# Power.net
KiCad netlist of a schematic drawn in Altium Designer
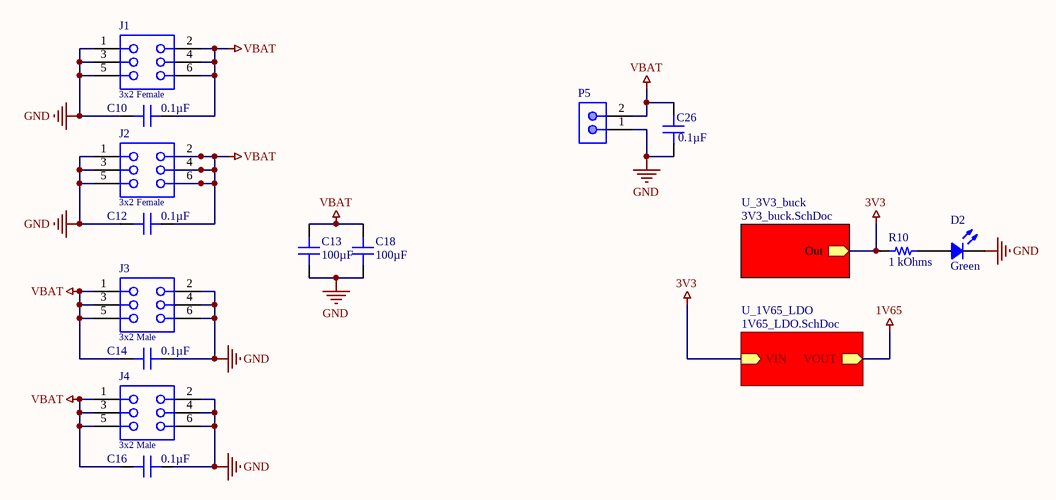
[diagram p0: Power.SchDoc]

(export (version "E")
  (design (tool "Eeschema 10.0.6"))
  (components
    (comp (ref "C10")
      (value "0.1µF")
      (footprint "CAP 0603_1608")
      (description "CAP CER 0.1UF 100V 0603 EPOXY")
      (fields
        (field (name "PART NUMBER") "GCG188R92A104KA03D")
        (field (name "MANUFACTURER") "Murata Electronics")
      )
      (libsource (lib "Celestial Altium Library - altium_library") (part "Capacitor"))
    )
    (comp (ref "C12")
      (value "0.1µF")
      (footprint "CAP 0603_1608")
      (description "CAP CER 0.1UF 100V 0603 EPOXY")
      (fields
        (field (name "PART NUMBER") "GCG188R92A104KA03D")
        (field (name "MANUFACTURER") "Murata Electronics")
      )
      (libsource (lib "Celestial Altium Library - altium_library") (part "Capacitor"))
    )
    (comp (ref "C13")
      (value "100µF")
      (footprint "CAP 1210_3225 - 2.8MM")
      (description "CAP CER 100UF 16V X5R 1210")
      (fields (field (name "PART NUMBER") "EMK325ABJ107MM-P") (field (name "MANUFACTURER") "Taiyo Yuden"))
      (libsource (lib "Celestial Altium Library - altium_library") (part "Capacitor"))
    )
    (comp (ref "C14")
      (value "0.1µF")
      (footprint "CAP 0603_1608")
      (description "CAP CER 0.1UF 100V 0603 EPOXY")
      (fields
        (field (name "PART NUMBER") "GCG188R92A104KA03D")
        (field (name "MANUFACTURER") "Murata Electronics")
      )
      (libsource (lib "Celestial Altium Library - altium_library") (part "Capacitor"))
    )
    (comp (ref "C16")
      (value "0.1µF")
      (footprint "CAP 0603_1608")
      (description "CAP CER 0.1UF 100V 0603 EPOXY")
      (fields
        (field (name "PART NUMBER") "GCG188R92A104KA03D")
        (field (name "MANUFACTURER") "Murata Electronics")
      )
      (libsource (lib "Celestial Altium Library - altium_library") (part "Capacitor"))
    )
    (comp (ref "C18")
      (value "100µF")
      (footprint "CAP 1210_3225 - 2.8MM")
      (description "CAP CER 100UF 16V X5R 1210")
      (fields (field (name "PART NUMBER") "EMK325ABJ107MM-P") (field (name "MANUFACTURER") "Taiyo Yuden"))
      (libsource (lib "Celestial Altium Library - altium_library") (part "Capacitor"))
    )
    (comp (ref "C26")
      (value "0.1µF")
      (footprint "CAP 0603_1608")
      (description "CAP CER 0.1UF 100V 0603 EPOXY")
      (fields
        (field (name "PART NUMBER") "GCG188R92A104KA03D")
        (field (name "MANUFACTURER") "Murata Electronics")
      )
      (libsource (lib "Celestial Altium Library - altium_library") (part "Capacitor"))
    )
    (comp (ref "D2")
      (value "Green")
      (footprint "LED 0603_1608 GREEN")
      (description "1.6X0.8MM LC GREEN PIXSOLED DOME")
      (fields (field (name "PART NUMBER") "XZCDGK53W-8VF") (field (name "MANUFACTURER") "SunLED"))
      (libsource (lib "Celestial Altium Library - altium_library") (part "LED"))
    )
    (comp (ref "J1")
      (value "3x2 Female")
      (footprint "62000621821")
      (description "WR-PHD Socket Header, THT, pitch 2mm, Dual Row, Vertical, 6p")
      (fields
        (field (name "MANUFACTURER PART NUMBER") "62000621821")
        (field (name "MANUFACTURER") "Wurth Elektronik")
      )
      (libsource (lib "Altium_WR-PHD") (part "62000621821"))
    )
    (comp (ref "J2")
      (value "3x2 Female")
      (footprint "62000621821")
      (description "WR-PHD Socket Header, THT, pitch 2mm, Dual Row, Vertical, 6p")
      (fields
        (field (name "MANUFACTURER PART NUMBER") "62000621821")
        (field (name "MANUFACTURER") "Wurth Elektronik")
      )
      (libsource (lib "Altium_WR-PHD") (part "62000621821"))
    )
    (comp (ref "J3")
      (value "3x2 Male")
      (footprint "2mm 3x2 Male Right - duplicate")
      (description "2mm Male 3x2 Right")
      (fields
        (field (name "MANUFACTURER PART NUMBER") "62000621821")
        (field (name "MANUFACTURER") "Wurth Elektronik")
      )
      (libsource (lib "IC") (part "2mm Male 3x2 Right"))
    )
    (comp (ref "J4")
      (value "3x2 Male")
      (footprint "2mm 3x2 Male Right - duplicate")
      (description "2mm Male 3x2 Right")
      (fields
        (field (name "MANUFACTURER PART NUMBER") "62000621821")
        (field (name "MANUFACTURER") "Wurth Elektronik")
      )
      (libsource (lib "IC") (part "2mm Male 3x2 Right"))
    )
    (comp (ref "P5")
      (value "2 pin 2mm JST Male")
      (footprint "2pin - 2mm JST male")
      (libsource (lib "IC") (part "2 pin 2mm JST Male"))
    )
    (comp (ref "R10")
      (value "1 kOhms")
      (footprint "RES 0603_1608")
      (description "RES 1K OHM 0.5% 1/10W 0603")
      (fields
        (field (name "PART NUMBER") "RNCF0603DTE1K00")
        (field (name "MANUFACTURER") "Stackpole Electronics Inc")
      )
      (libsource (lib "Celestial Altium Library - altium_library") (part "Resistor"))
    )
  )
  (nets
    (net (code "2") (name "3V3") (class "Default")
      (node (ref "R10") (pin "1") (pinfunction "1_1") (pintype "passive"))
    )
    (net (code "3") (name "GND") (class "Default")
      (node (ref "C10") (pin "1") (pinfunction "1_1") (pintype "passive"))
      (node (ref "C12") (pin "1") (pinfunction "1_1") (pintype "passive"))
      (node (ref "C13") (pin "1") (pinfunction "1_1") (pintype "passive"))
      (node (ref "C14") (pin "2") (pinfunction "2_2") (pintype "passive"))
      (node (ref "C16") (pin "2") (pinfunction "2_2") (pintype "passive"))
      (node (ref "C18") (pin "1") (pinfunction "1_1") (pintype "passive"))
      (node (ref "C26") (pin "2") (pinfunction "2_2") (pintype "passive"))
      (node (ref "D2") (pin "2") (pinfunction "2_2") (pintype "passive"))
      (node (ref "J1") (pin "1") (pinfunction "1_1") (pintype "passive"))
      (node (ref "J1") (pin "3") (pinfunction "3_3") (pintype "passive"))
      (node (ref "J1") (pin "5") (pinfunction "5_5") (pintype "passive"))
      (node (ref "J2") (pin "1") (pinfunction "1_1") (pintype "passive"))
      (node (ref "J2") (pin "3") (pinfunction "3_3") (pintype "passive"))
      (node (ref "J2") (pin "5") (pinfunction "5_5") (pintype "passive"))
      (node (ref "J3") (pin "2") (pinfunction "2_2") (pintype "passive"))
      (node (ref "J3") (pin "4") (pinfunction "4_4") (pintype "passive"))
      (node (ref "J3") (pin "6") (pinfunction "6_6") (pintype "passive"))
      (node (ref "J4") (pin "2") (pinfunction "2_2") (pintype "passive"))
      (node (ref "J4") (pin "4") (pinfunction "4_4") (pintype "passive"))
      (node (ref "J4") (pin "6") (pinfunction "6_6") (pintype "passive"))
      (node (ref "P5") (pin "1") (pinfunction "1_1") (pintype "passive"))
    )
    (net (code "4") (name "Net-(D2-Pad1)") (class "Default")
      (node (ref "D2") (pin "1") (pinfunction "1_1") (pintype "passive"))
      (node (ref "R10") (pin "2") (pinfunction "2_2") (pintype "passive"))
    )
    (net (code "5") (name "VBAT") (class "Default")
      (node (ref "C10") (pin "2") (pinfunction "2_2") (pintype "passive"))
      (node (ref "C12") (pin "2") (pinfunction "2_2") (pintype "passive"))
      (node (ref "C13") (pin "2") (pinfunction "2_2") (pintype "passive"))
      (node (ref "C14") (pin "1") (pinfunction "1_1") (pintype "passive"))
      (node (ref "C16") (pin "1") (pinfunction "1_1") (pintype "passive"))
      (node (ref "C18") (pin "2") (pinfunction "2_2") (pintype "passive"))
      (node (ref "C26") (pin "1") (pinfunction "1_1") (pintype "passive"))
      (node (ref "J1") (pin "2") (pinfunction "2_2") (pintype "passive"))
      (node (ref "J1") (pin "4") (pinfunction "4_4") (pintype "passive"))
      (node (ref "J1") (pin "6") (pinfunction "6_6") (pintype "passive"))
      (node (ref "J2") (pin "2") (pinfunction "2_2") (pintype "passive"))
      (node (ref "J2") (pin "4") (pinfunction "4_4") (pintype "passive"))
      (node (ref "J2") (pin "6") (pinfunction "6_6") (pintype "passive"))
      (node (ref "J3") (pin "1") (pinfunction "1_1") (pintype "passive"))
      (node (ref "J3") (pin "3") (pinfunction "3_3") (pintype "passive"))
      (node (ref "J3") (pin "5") (pinfunction "5_5") (pintype "passive"))
      (node (ref "J4") (pin "1") (pinfunction "1_1") (pintype "passive"))
      (node (ref "J4") (pin "3") (pinfunction "3_3") (pintype "passive"))
      (node (ref "J4") (pin "5") (pinfunction "5_5") (pintype "passive"))
      (node (ref "P5") (pin "2") (pinfunction "2_2") (pintype "passive"))
    )
  )
)
